# G1-3.net
KiCad netlist of a schematic drawn in EAGLE
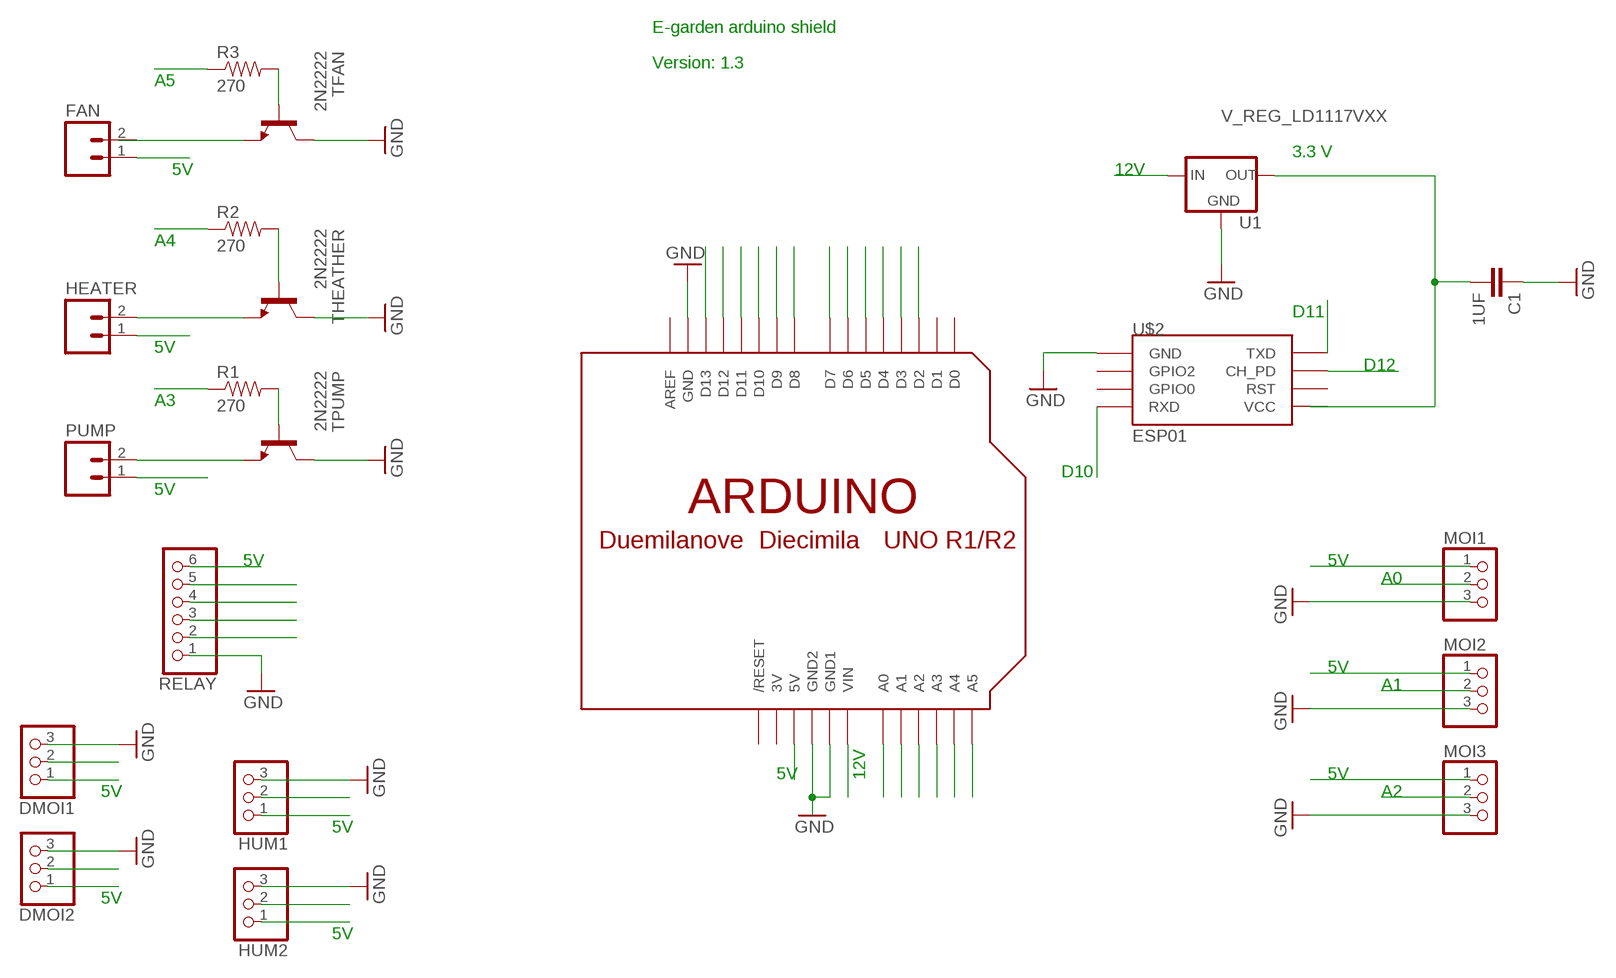
[diagram p0: schematic, sheet 1]

(export (version "E")
  (design (tool "Eeschema 10.0.6"))
  (components
    (comp (ref "C1")
      (value "1UF")
      (footprint "eagle-import:CAP-PTH-SMALL-KIT")
      (libsource (lib "eagle-import") (part "CAPKIT"))
    )
    (comp (ref "DMOI1")
      (value "PINHD-1X3CB")
      (footprint "eagle-import:1X03-CLEANBIG")
      (libsource (lib "eagle-import") (part "PINHD-1X3CB"))
    )
    (comp (ref "DMOI2")
      (value "PINHD-1X3CB")
      (footprint "eagle-import:1X03-CLEANBIG")
      (libsource (lib "eagle-import") (part "PINHD-1X3CB"))
    )
    (comp (ref "FAN")
      (value "M02PTH")
      (footprint "eagle-import:1X02")
      (libsource (lib "eagle-import") (part "M02PTH"))
    )
    (comp (ref "HEATER")
      (value "M02PTH")
      (footprint "eagle-import:1X02")
      (libsource (lib "eagle-import") (part "M02PTH"))
    )
    (comp (ref "HUM1")
      (value "PINHD-1X3CB")
      (footprint "eagle-import:1X03-CLEANBIG")
      (libsource (lib "eagle-import") (part "PINHD-1X3CB"))
    )
    (comp (ref "HUM2")
      (value "PINHD-1X3CB")
      (footprint "eagle-import:1X03-CLEANBIG")
      (libsource (lib "eagle-import") (part "PINHD-1X3CB"))
    )
    (comp (ref "MOI1")
      (value "PINHD-1X3CB")
      (footprint "eagle-import:1X03-CLEANBIG")
      (libsource (lib "eagle-import") (part "PINHD-1X3CB"))
    )
    (comp (ref "MOI2")
      (value "PINHD-1X3CB")
      (footprint "eagle-import:1X03-CLEANBIG")
      (libsource (lib "eagle-import") (part "PINHD-1X3CB"))
    )
    (comp (ref "MOI3")
      (value "PINHD-1X3CB")
      (footprint "eagle-import:1X03-CLEANBIG")
      (libsource (lib "eagle-import") (part "PINHD-1X3CB"))
    )
    (comp (ref "PUMP")
      (value "M02PTH")
      (footprint "eagle-import:1X02")
      (libsource (lib "eagle-import") (part "M02PTH"))
    )
    (comp (ref "R1")
      (value "270")
      (footprint "eagle-import:AXIAL-0.4")
      (libsource (lib "eagle-import") (part "RESISTORPTH-1/4W"))
    )
    (comp (ref "R2")
      (value "270")
      (footprint "eagle-import:AXIAL-0.4")
      (libsource (lib "eagle-import") (part "RESISTORPTH-1/4W"))
    )
    (comp (ref "R3")
      (value "270")
      (footprint "eagle-import:AXIAL-0.4")
      (libsource (lib "eagle-import") (part "RESISTORPTH-1/4W"))
    )
    (comp (ref "RELAY")
      (value "PINHD-1X6CB")
      (footprint "eagle-import:1X06-CLEANBIG")
      (libsource (lib "eagle-import") (part "PINHD-1X6CB"))
    )
    (comp (ref "TFAN")
      (value "2N2222")
      (footprint "eagle-import:TO92-EBC-OVAL")
      (libsource (lib "eagle-import") (part "2N2222"))
    )
    (comp (ref "THEATHER")
      (value "2N2222")
      (footprint "eagle-import:TO92-EBC-OVAL")
      (libsource (lib "eagle-import") (part "2N2222"))
    )
    (comp (ref "TPUMP")
      (value "2N2222")
      (footprint "eagle-import:TO92-EBC-OVAL")
      (libsource (lib "eagle-import") (part "2N2222"))
    )
    (comp (ref "U$1")
      (value "ARDUINO-BPLACE")
      (footprint "eagle-import:ARDUINO-BPLACE")
      (libsource (lib "eagle-import") (part "ARDUINO-BPLACE"))
    )
    (comp (ref "U$2")
      (value "ESP01")
      (footprint "eagle-import:ESP01")
      (libsource (lib "eagle-import") (part "ESP01"))
    )
    (comp (ref "U1")
      (value "V_REG_LD1117VXX")
      (footprint "eagle-import:78XXL")
      (libsource (lib "eagle-import") (part "V_REG_LD1117VXX"))
    )
  )
  (nets
    (net (code "1") (name "/3V") (class "Default")
      (node (ref "U$1") (pin "3V") (pinfunction "3V_3V") (pintype "power_in"))
    )
    (net (code "2") (name "/A0") (class "Default")
      (node (ref "MOI1") (pin "2") (pinfunction "2_2") (pintype "passive"))
      (node (ref "U$1") (pin "A0") (pinfunction "A0_A0") (pintype "bidirectional"))
    )
    (net (code "3") (name "/A1") (class "Default")
      (node (ref "MOI2") (pin "2") (pinfunction "2_2") (pintype "passive"))
      (node (ref "U$1") (pin "A1") (pinfunction "A1_A1") (pintype "bidirectional"))
    )
    (net (code "4") (name "/A2") (class "Default")
      (node (ref "MOI3") (pin "2") (pinfunction "2_2") (pintype "passive"))
      (node (ref "U$1") (pin "A2") (pinfunction "A2_A2") (pintype "bidirectional"))
    )
    (net (code "5") (name "/A3") (class "Default")
      (node (ref "R1") (pin "P$1") (pinfunction "1_P$1") (pintype "passive"))
      (node (ref "U$1") (pin "A3") (pinfunction "A3_A3") (pintype "bidirectional"))
    )
    (net (code "6") (name "/A4") (class "Default")
      (node (ref "R2") (pin "P$1") (pinfunction "1_P$1") (pintype "passive"))
      (node (ref "U$1") (pin "A4") (pinfunction "A4_A4") (pintype "bidirectional"))
    )
    (net (code "7") (name "/A5") (class "Default")
      (node (ref "R3") (pin "P$1") (pinfunction "1_P$1") (pintype "passive"))
      (node (ref "U$1") (pin "A5") (pinfunction "A5_A5") (pintype "bidirectional"))
    )
    (net (code "8") (name "/D2") (class "Default")
      (node (ref "HUM1") (pin "2") (pinfunction "2_2") (pintype "passive"))
      (node (ref "U$1") (pin "D2") (pinfunction "D2_D2") (pintype "bidirectional"))
    )
    (net (code "9") (name "/D3") (class "Default")
      (node (ref "HUM2") (pin "2") (pinfunction "2_2") (pintype "passive"))
      (node (ref "U$1") (pin "D3") (pinfunction "D3_D3") (pintype "bidirectional"))
    )
    (net (code "10") (name "/D4") (class "Default")
      (node (ref "DMOI1") (pin "2") (pinfunction "2_2") (pintype "passive"))
      (node (ref "U$1") (pin "D4") (pinfunction "D4_D4") (pintype "bidirectional"))
    )
    (net (code "11") (name "/D5") (class "Default")
      (node (ref "DMOI2") (pin "2") (pinfunction "2_2") (pintype "passive"))
      (node (ref "U$1") (pin "D5") (pinfunction "D5_D5") (pintype "bidirectional"))
    )
    (net (code "12") (name "/D6") (class "Default")
      (node (ref "RELAY") (pin "2") (pinfunction "2_2") (pintype "passive"))
      (node (ref "U$1") (pin "D6") (pinfunction "D6_D6") (pintype "bidirectional"))
    )
    (net (code "13") (name "/D7") (class "Default")
      (node (ref "RELAY") (pin "3") (pinfunction "3_3") (pintype "passive"))
      (node (ref "U$1") (pin "D7") (pinfunction "D7_D7") (pintype "bidirectional"))
    )
    (net (code "14") (name "/D8") (class "Default")
      (node (ref "RELAY") (pin "4") (pinfunction "4_4") (pintype "passive"))
      (node (ref "U$1") (pin "D8") (pinfunction "D8_D8") (pintype "bidirectional"))
    )
    (net (code "15") (name "/D9") (class "Default")
      (node (ref "RELAY") (pin "5") (pinfunction "5_5") (pintype "passive"))
      (node (ref "U$1") (pin "D9") (pinfunction "D9_D9") (pintype "bidirectional"))
    )
    (net (code "16") (name "/D10") (class "Default")
      (node (ref "U$1") (pin "D10") (pinfunction "D10_D10") (pintype "bidirectional"))
      (node (ref "U$2") (pin "RX") (pinfunction "RXD_RX") (pintype "bidirectional"))
    )
    (net (code "17") (name "/D11") (class "Default")
      (node (ref "U$1") (pin "D11") (pinfunction "D11_D11") (pintype "bidirectional"))
      (node (ref "U$2") (pin "TX") (pinfunction "TXD_TX") (pintype "bidirectional"))
    )
    (net (code "18") (name "/D12") (class "Default")
      (node (ref "U$1") (pin "D12") (pinfunction "D12_D12") (pintype "bidirectional"))
      (node (ref "U$2") (pin "CH_PD") (pinfunction "CH_PD_CH_PD") (pintype "bidirectional"))
    )
    (net (code "19") (name "/V5") (class "Default")
      (node (ref "DMOI1") (pin "1") (pinfunction "1_1") (pintype "passive"))
      (node (ref "DMOI2") (pin "1") (pinfunction "1_1") (pintype "passive"))
      (node (ref "FAN") (pin "1") (pinfunction "1_1") (pintype "passive"))
      (node (ref "HEATER") (pin "1") (pinfunction "1_1") (pintype "passive"))
      (node (ref "HUM1") (pin "1") (pinfunction "1_1") (pintype "passive"))
      (node (ref "HUM2") (pin "1") (pinfunction "1_1") (pintype "passive"))
      (node (ref "MOI1") (pin "1") (pinfunction "1_1") (pintype "passive"))
      (node (ref "MOI2") (pin "1") (pinfunction "1_1") (pintype "passive"))
      (node (ref "MOI3") (pin "1") (pinfunction "1_1") (pintype "passive"))
      (node (ref "PUMP") (pin "1") (pinfunction "1_1") (pintype "passive"))
      (node (ref "RELAY") (pin "6") (pinfunction "6_6") (pintype "passive"))
      (node (ref "U$1") (pin "5V") (pinfunction "5V_5V") (pintype "power_in"))
    )
    (net (code "20") (name "/V12") (class "Default")
      (node (ref "U$1") (pin "VIN") (pinfunction "VIN_VIN") (pintype "power_in"))
      (node (ref "U1") (pin "OUT") (pinfunction "IN_OUT") (pintype "input"))
    )
    (net (code "21") (name "GND") (class "Default")
      (node (ref "C1") (pin "1") (pinfunction "1_1") (pintype "passive"))
      (node (ref "DMOI1") (pin "3") (pinfunction "3_3") (pintype "passive"))
      (node (ref "DMOI2") (pin "3") (pinfunction "3_3") (pintype "passive"))
      (node (ref "HUM1") (pin "3") (pinfunction "3_3") (pintype "passive"))
      (node (ref "HUM2") (pin "3") (pinfunction "3_3") (pintype "passive"))
      (node (ref "MOI1") (pin "3") (pinfunction "3_3") (pintype "passive"))
      (node (ref "MOI2") (pin "3") (pinfunction "3_3") (pintype "passive"))
      (node (ref "MOI3") (pin "3") (pinfunction "3_3") (pintype "passive"))
      (node (ref "RELAY") (pin "1") (pinfunction "1_1") (pintype "passive"))
      (node (ref "TFAN") (pin "C") (pinfunction "C_C") (pintype "passive"))
      (node (ref "THEATHER") (pin "C") (pinfunction "C_C") (pintype "passive"))
      (node (ref "TPUMP") (pin "C") (pinfunction "C_C") (pintype "passive"))
      (node (ref "U$1") (pin "GND") (pinfunction "GND_GND") (pintype "power_in"))
      (node (ref "U$1") (pin "GND1") (pinfunction "GND1_GND1") (pintype "power_in"))
      (node (ref "U$1") (pin "GND2") (pinfunction "GND2_GND2") (pintype "power_in"))
      (node (ref "U$2") (pin "GND") (pinfunction "GND_GND") (pintype "bidirectional"))
      (node (ref "U1") (pin "IN") (pinfunction "GND_IN") (pintype "input"))
    )
    (net (code "22") (name "Net-(FAN-Pad2)") (class "Default")
      (node (ref "FAN") (pin "2") (pinfunction "2_2") (pintype "passive"))
      (node (ref "TFAN") (pin "E") (pinfunction "E_E") (pintype "passive"))
    )
    (net (code "23") (name "Net-(HEATER-Pad2)") (class "Default")
      (node (ref "HEATER") (pin "2") (pinfunction "2_2") (pintype "passive"))
      (node (ref "THEATHER") (pin "E") (pinfunction "E_E") (pintype "passive"))
    )
    (net (code "24") (name "Net-(PUMP-Pad2)") (class "Default")
      (node (ref "PUMP") (pin "2") (pinfunction "2_2") (pintype "passive"))
      (node (ref "TPUMP") (pin "E") (pinfunction "E_E") (pintype "passive"))
    )
    (net (code "25") (name "Net-(R1-2)") (class "Default")
      (node (ref "R1") (pin "P$2") (pinfunction "2_P$2") (pintype "passive"))
      (node (ref "TPUMP") (pin "B") (pinfunction "B_B") (pintype "passive"))
    )
    (net (code "26") (name "Net-(R2-2)") (class "Default")
      (node (ref "R2") (pin "P$2") (pinfunction "2_P$2") (pintype "passive"))
      (node (ref "THEATHER") (pin "B") (pinfunction "B_B") (pintype "passive"))
    )
    (net (code "27") (name "Net-(R3-2)") (class "Default")
      (node (ref "R3") (pin "P$2") (pinfunction "2_P$2") (pintype "passive"))
      (node (ref "TFAN") (pin "B") (pinfunction "B_B") (pintype "passive"))
    )
    (net (code "28") (name "Net-(U1-OUT)") (class "Default")
      (node (ref "C1") (pin "2") (pinfunction "2_2") (pintype "passive"))
      (node (ref "U$2") (pin "VCC") (pinfunction "VCC_VCC") (pintype "bidirectional"))
      (node (ref "U1") (pin "GND") (pinfunction "OUT_GND") (pintype "passive"))
    )
    (net (code "29") (name "unconnected-(U$1-PadAREF)") (class "Default")
      (node (ref "U$1") (pin "AREF") (pinfunction "AREF_AREF") (pintype "bidirectional"))
    )
    (net (code "30") (name "unconnected-(U$1-PadD0)") (class "Default")
      (node (ref "U$1") (pin "D0") (pinfunction "D0_D0") (pintype "bidirectional"))
    )
    (net (code "31") (name "unconnected-(U$1-PadD1)") (class "Default")
      (node (ref "U$1") (pin "D1") (pinfunction "D1_D1") (pintype "bidirectional"))
    )
    (net (code "32") (name "unconnected-(U$1-PadD13)") (class "Default")
      (node (ref "U$1") (pin "D13") (pinfunction "D13_D13") (pintype "bidirectional"))
    )
    (net (code "33") (name "unconnected-(U$1-{slash}RESET-PadRESET)") (class "Default")
      (node (ref "U$1") (pin "RESET") (pinfunction "/RESET_RESET") (pintype "bidirectional"))
    )
    (net (code "34") (name "unconnected-(U$2-PadGPIO0)") (class "Default")
      (node (ref "U$2") (pin "GPIO0") (pinfunction "GPIO0_GPIO0") (pintype "bidirectional"))
    )
    (net (code "35") (name "unconnected-(U$2-PadGPIO2)") (class "Default")
      (node (ref "U$2") (pin "GPIO2") (pinfunction "GPIO2_GPIO2") (pintype "bidirectional"))
    )
    (net (code "36") (name "unconnected-(U$2-PadRST)") (class "Default")
      (node (ref "U$2") (pin "RST") (pinfunction "RST_RST") (pintype "bidirectional"))
    )
  )
)
